# breakout.net
KiCad netlist of a schematic drawn in EAGLE
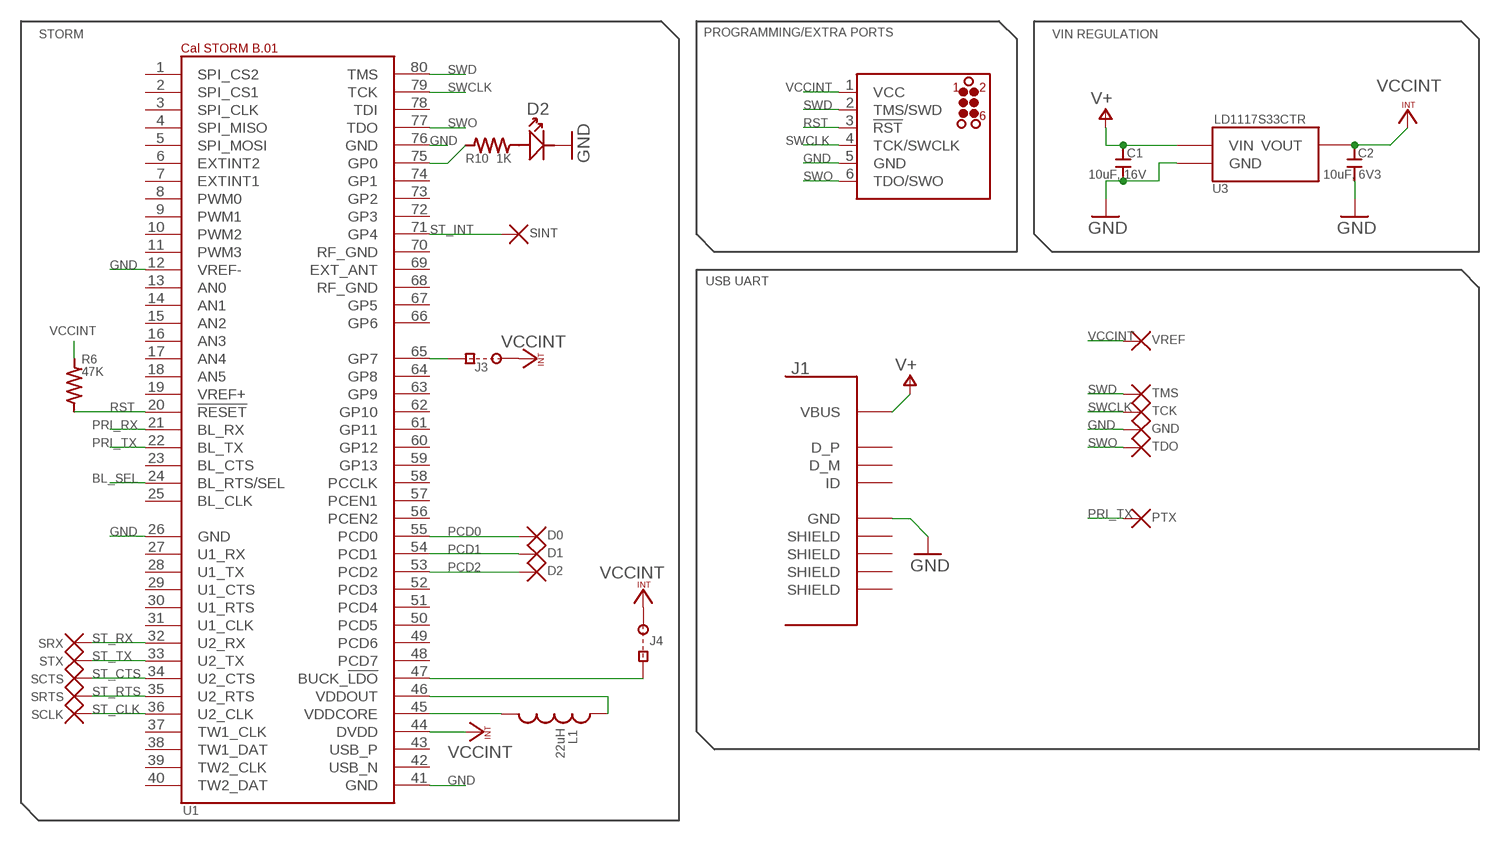
[diagram p0: schematic, sheet 1]

(export (version "E")
  (design (tool "Eeschema 10.0.6"))
  (components
    (comp (ref "C1")
      (value "10uF, 16V")
      (footprint "eagle-import:0805")
      (libsource (lib "eagle-import") (part "0805_CAPACITOR"))
    )
    (comp (ref "C2")
      (value "10uF, 6V3")
      (footprint "eagle-import:C0603")
      (libsource (lib "eagle-import") (part "0603_CAPACITOR"))
    )
    (comp (ref "D2")
      (value "STATLED")
      (footprint "eagle-import:LINE_0805")
      (libsource (lib "eagle-import") (part "STATLED"))
    )
    (comp (ref "J1")
      (value "USBSMT")
      (footprint "eagle-import:USB_SMT")
      (libsource (lib "eagle-import") (part "USBSMT"))
    )
    (comp (ref "J3")
      (value "CUTJ")
      (footprint "eagle-import:CUT")
      (libsource (lib "eagle-import") (part "CUTJ"))
    )
    (comp (ref "J4")
      (value "CUTJ")
      (footprint "eagle-import:CUT")
      (libsource (lib "eagle-import") (part "CUTJ"))
    )
    (comp (ref "J8")
      (value "JLINK_CONNECT")
      (footprint "eagle-import:TC2030-MCP-NL")
      (libsource (lib "eagle-import") (part "JLINK_CONNECT"))
    )
    (comp (ref "L1")
      (value "22uH")
      (footprint "eagle-import:SRN4018")
      (libsource (lib "eagle-import") (part "SRN4018"))
    )
    (comp (ref "R6")
      (value "47K")
      (footprint "eagle-import:C0402")
      (libsource (lib "eagle-import") (part "0603_RESISTOR0402"))
    )
    (comp (ref "R10")
      (value "1K")
      (footprint "eagle-import:C0402")
      (libsource (lib "eagle-import") (part "0603_RESISTOR0402"))
    )
    (comp (ref "TP1")
      (value "VREF")
      (footprint "eagle-import:TPP")
      (libsource (lib "eagle-import") (part "TP"))
    )
    (comp (ref "TP4")
      (value "TMS")
      (footprint "eagle-import:TPP")
      (libsource (lib "eagle-import") (part "TP"))
    )
    (comp (ref "TP5")
      (value "TCK")
      (footprint "eagle-import:TPP")
      (libsource (lib "eagle-import") (part "TP"))
    )
    (comp (ref "TP6")
      (value "GND")
      (footprint "eagle-import:TPP")
      (libsource (lib "eagle-import") (part "TP"))
    )
    (comp (ref "TP7")
      (value "TDO")
      (footprint "eagle-import:TPP")
      (libsource (lib "eagle-import") (part "TP"))
    )
    (comp (ref "TP10")
      (value "D2")
      (footprint "eagle-import:TPP")
      (libsource (lib "eagle-import") (part "TP"))
    )
    (comp (ref "TP11")
      (value "D1")
      (footprint "eagle-import:TPP")
      (libsource (lib "eagle-import") (part "TP"))
    )
    (comp (ref "TP12")
      (value "D0")
      (footprint "eagle-import:TPP")
      (libsource (lib "eagle-import") (part "TP"))
    )
    (comp (ref "TP13")
      (value "SRX")
      (footprint "eagle-import:TPP")
      (libsource (lib "eagle-import") (part "TP"))
    )
    (comp (ref "TP14")
      (value "STX")
      (footprint "eagle-import:TPP")
      (libsource (lib "eagle-import") (part "TP"))
    )
    (comp (ref "TP15")
      (value "SCTS")
      (footprint "eagle-import:TPP")
      (libsource (lib "eagle-import") (part "TP"))
    )
    (comp (ref "TP16")
      (value "SRTS")
      (footprint "eagle-import:TPP")
      (libsource (lib "eagle-import") (part "TP"))
    )
    (comp (ref "TP17")
      (value "SCLK")
      (footprint "eagle-import:TPP")
      (libsource (lib "eagle-import") (part "TP"))
    )
    (comp (ref "TP18")
      (value "SINT")
      (footprint "eagle-import:TPP")
      (libsource (lib "eagle-import") (part "TP"))
    )
    (comp (ref "TX")
      (value "PTX")
      (footprint "eagle-import:TPP")
      (libsource (lib "eagle-import") (part "TP"))
    )
    (comp (ref "U1")
      (value "STORM_B.01")
      (footprint "eagle-import:STORM_LANDING")
      (libsource (lib "eagle-import") (part "STORM_B.01"))
    )
    (comp (ref "U3")
      (value "LD1117S33CTR_3V3_REG")
      (footprint "eagle-import:SOT223")
      (libsource (lib "eagle-import") (part "LD1117S33CTR_3V3_REG"))
    )
  )
  (nets
    (net (code "1") (name "/BL_SEL") (class "Default")
      (node (ref "U1") (pin "24") (pinfunction "BL_RTS/SEL_24") (pintype "bidirectional"))
    )
    (net (code "2") (name "/PCD0") (class "Default")
      (node (ref "TP12") (pin "P$1") (pinfunction "P$1_P$1") (pintype "bidirectional"))
      (node (ref "U1") (pin "55") (pinfunction "PCD0_55") (pintype "bidirectional"))
    )
    (net (code "3") (name "/PCD1") (class "Default")
      (node (ref "TP11") (pin "P$1") (pinfunction "P$1_P$1") (pintype "bidirectional"))
      (node (ref "U1") (pin "54") (pinfunction "PCD1_54") (pintype "bidirectional"))
    )
    (net (code "4") (name "/PCD2") (class "Default")
      (node (ref "TP10") (pin "P$1") (pinfunction "P$1_P$1") (pintype "bidirectional"))
      (node (ref "U1") (pin "53") (pinfunction "PCD2_53") (pintype "bidirectional"))
    )
    (net (code "5") (name "/PRI_RX") (class "Default")
      (node (ref "U1") (pin "21") (pinfunction "BL_RX_21") (pintype "bidirectional"))
    )
    (net (code "6") (name "/PRI_TX") (class "Default")
      (node (ref "TX") (pin "P$1") (pinfunction "P$1_P$1") (pintype "bidirectional"))
      (node (ref "U1") (pin "22") (pinfunction "BL_TX_22") (pintype "bidirectional"))
    )
    (net (code "7") (name "/RST") (class "Default")
      (node (ref "J8") (pin "3") (pinfunction "~{RST}_3") (pintype "bidirectional"))
      (node (ref "R6") (pin "2") (pinfunction "P$2_2") (pintype "passive"))
      (node (ref "U1") (pin "20") (pinfunction "~{RESET}_20") (pintype "bidirectional"))
    )
    (net (code "8") (name "/ST_CLK") (class "Default")
      (node (ref "TP17") (pin "P$1") (pinfunction "P$1_P$1") (pintype "bidirectional"))
      (node (ref "U1") (pin "36") (pinfunction "U2_CLK_36") (pintype "bidirectional"))
    )
    (net (code "9") (name "/ST_CTS") (class "Default")
      (node (ref "TP15") (pin "P$1") (pinfunction "P$1_P$1") (pintype "bidirectional"))
      (node (ref "U1") (pin "34") (pinfunction "U2_CTS_34") (pintype "bidirectional"))
    )
    (net (code "10") (name "/ST_INT") (class "Default")
      (node (ref "TP18") (pin "P$1") (pinfunction "P$1_P$1") (pintype "bidirectional"))
      (node (ref "U1") (pin "71") (pinfunction "GP4_71") (pintype "bidirectional"))
    )
    (net (code "11") (name "/ST_RTS") (class "Default")
      (node (ref "TP16") (pin "P$1") (pinfunction "P$1_P$1") (pintype "bidirectional"))
      (node (ref "U1") (pin "35") (pinfunction "U2_RTS_35") (pintype "bidirectional"))
    )
    (net (code "12") (name "/ST_RX") (class "Default")
      (node (ref "TP13") (pin "P$1") (pinfunction "P$1_P$1") (pintype "bidirectional"))
      (node (ref "U1") (pin "32") (pinfunction "U2_RX_32") (pintype "bidirectional"))
    )
    (net (code "13") (name "/ST_TX") (class "Default")
      (node (ref "TP14") (pin "P$1") (pinfunction "P$1_P$1") (pintype "bidirectional"))
      (node (ref "U1") (pin "33") (pinfunction "U2_TX_33") (pintype "bidirectional"))
    )
    (net (code "14") (name "/SWCLK") (class "Default")
      (node (ref "J8") (pin "4") (pinfunction "TCK/SWCLK_4") (pintype "bidirectional"))
      (node (ref "TP5") (pin "P$1") (pinfunction "P$1_P$1") (pintype "bidirectional"))
      (node (ref "U1") (pin "79") (pinfunction "TCK_79") (pintype "bidirectional"))
    )
    (net (code "15") (name "/SWD") (class "Default")
      (node (ref "J8") (pin "2") (pinfunction "TMS/SWD_2") (pintype "bidirectional"))
      (node (ref "TP4") (pin "P$1") (pinfunction "P$1_P$1") (pintype "bidirectional"))
      (node (ref "U1") (pin "80") (pinfunction "TMS_80") (pintype "bidirectional"))
    )
    (net (code "16") (name "/SWO") (class "Default")
      (node (ref "J8") (pin "6") (pinfunction "TDO/SWO_6") (pintype "bidirectional"))
      (node (ref "TP7") (pin "P$1") (pinfunction "P$1_P$1") (pintype "bidirectional"))
      (node (ref "U1") (pin "77") (pinfunction "TDO_77") (pintype "bidirectional"))
    )
    (net (code "17") (name "GND") (class "Default")
      (node (ref "C1") (pin "1") (pinfunction "P$1_1") (pintype "passive"))
      (node (ref "C2") (pin "1") (pinfunction "P$1_1") (pintype "passive"))
      (node (ref "D2") (pin "LINE") (pinfunction "-_LINE") (pintype "passive"))
      (node (ref "J1") (pin "5GND") (pinfunction "GND_5GND") (pintype "bidirectional"))
      (node (ref "J8") (pin "5") (pinfunction "GND_5") (pintype "power_in"))
      (node (ref "TP6") (pin "P$1") (pinfunction "P$1_P$1") (pintype "bidirectional"))
      (node (ref "U1") (pin "12") (pinfunction "VREF-_12") (pintype "bidirectional"))
      (node (ref "U1") (pin "26") (pinfunction "GND_26") (pintype "bidirectional"))
      (node (ref "U1") (pin "41") (pinfunction "GND_41") (pintype "bidirectional"))
      (node (ref "U1") (pin "76") (pinfunction "GND_76") (pintype "bidirectional"))
      (node (ref "U3") (pin "1") (pinfunction "GND_1") (pintype "bidirectional"))
    )
    (net (code "18") (name "Net-(D2-+)") (class "Default")
      (node (ref "D2") (pin "NOLINE") (pinfunction "+_NOLINE") (pintype "passive"))
      (node (ref "R10") (pin "2") (pinfunction "P$2_2") (pintype "passive"))
    )
    (net (code "19") (name "Net-(R10-P$1)") (class "Default")
      (node (ref "R10") (pin "1") (pinfunction "P$1_1") (pintype "passive"))
      (node (ref "U1") (pin "75") (pinfunction "GP0_75") (pintype "bidirectional"))
    )
    (net (code "20") (name "Net-(U1-BUCK_~{LDO})") (class "Default")
      (node (ref "J4") (pin "SQ") (pinfunction "SQ_SQ") (pintype "bidirectional"))
      (node (ref "U1") (pin "47") (pinfunction "BUCK_~{LDO}_47") (pintype "bidirectional"))
    )
    (net (code "21") (name "Net-(U1-GP7)") (class "Default")
      (node (ref "J3") (pin "SQ") (pinfunction "SQ_SQ") (pintype "bidirectional"))
      (node (ref "U1") (pin "65") (pinfunction "GP7_65") (pintype "bidirectional"))
    )
    (net (code "22") (name "Net-(U1-VDDCORE)") (class "Default")
      (node (ref "L1") (pin "P$2") (pinfunction "P$2_P$2") (pintype "passive"))
      (node (ref "U1") (pin "45") (pinfunction "VDDCORE_45") (pintype "bidirectional"))
    )
    (net (code "23") (name "Net-(U1-VDDOUT)") (class "Default")
      (node (ref "L1") (pin "P$1") (pinfunction "P$1_P$1") (pintype "passive"))
      (node (ref "U1") (pin "46") (pinfunction "VDDOUT_46") (pintype "bidirectional"))
    )
    (net (code "24") (name "V+") (class "Default")
      (node (ref "C1") (pin "2") (pinfunction "P$2_2") (pintype "passive"))
      (node (ref "J1") (pin "1VBUS") (pinfunction "VBUS_1VBUS") (pintype "bidirectional"))
      (node (ref "U3") (pin "3") (pinfunction "VIN_3") (pintype "bidirectional"))
    )
    (net (code "25") (name "VCCINT") (class "Default")
      (node (ref "C2") (pin "2") (pinfunction "P$2_2") (pintype "passive"))
      (node (ref "J3") (pin "R") (pinfunction "R_R") (pintype "bidirectional"))
      (node (ref "J4") (pin "R") (pinfunction "R_R") (pintype "bidirectional"))
      (node (ref "J8") (pin "1") (pinfunction "VCC_1") (pintype "passive"))
      (node (ref "R6") (pin "1") (pinfunction "P$1_1") (pintype "passive"))
      (node (ref "TP1") (pin "P$1") (pinfunction "P$1_P$1") (pintype "bidirectional"))
      (node (ref "U1") (pin "44") (pinfunction "DVDD_44") (pintype "bidirectional"))
      (node (ref "U3") (pin "2") (pinfunction "VOUT_2") (pintype "bidirectional"))
    )
    (net (code "26") (name "unconnected-(J1-D_M-Pad2D-)") (class "Default")
      (node (ref "J1") (pin "2D-") (pinfunction "D_M_2D-") (pintype "bidirectional"))
    )
    (net (code "27") (name "unconnected-(J1-D_P-Pad3D+)") (class "Default")
      (node (ref "J1") (pin "3D+") (pinfunction "D_P_3D+") (pintype "bidirectional"))
    )
    (net (code "28") (name "unconnected-(J1-ID-Pad4ID)") (class "Default")
      (node (ref "J1") (pin "4ID") (pinfunction "ID_4ID") (pintype "bidirectional"))
    )
    (net (code "29") (name "unconnected-(J1-SHIELD-PadSHIELD@1)") (class "Default")
      (node (ref "J1") (pin "SHIELD@1") (pinfunction "SHIELD_SHIELD@1") (pintype "no_connect"))
    )
    (net (code "30") (name "unconnected-(J1-SHIELD-PadSHIELD@2)") (class "Default")
      (node (ref "J1") (pin "SHIELD@2") (pinfunction "SHIELD_SHIELD@2") (pintype "no_connect"))
    )
    (net (code "31") (name "unconnected-(J1-SHIELD-PadSHIELD@3)") (class "Default")
      (node (ref "J1") (pin "SHIELD@3") (pinfunction "SHIELD_SHIELD@3") (pintype "no_connect"))
    )
    (net (code "32") (name "unconnected-(J1-SHIELD-PadSHIELD@4)") (class "Default")
      (node (ref "J1") (pin "SHIELD@4") (pinfunction "SHIELD_SHIELD@4") (pintype "no_connect"))
    )
    (net (code "33") (name "unconnected-(U1-AN0-Pad13)") (class "Default")
      (node (ref "U1") (pin "13") (pinfunction "AN0_13") (pintype "bidirectional"))
    )
    (net (code "34") (name "unconnected-(U1-AN1-Pad14)") (class "Default")
      (node (ref "U1") (pin "14") (pinfunction "AN1_14") (pintype "bidirectional"))
    )
    (net (code "35") (name "unconnected-(U1-AN2-Pad15)") (class "Default")
      (node (ref "U1") (pin "15") (pinfunction "AN2_15") (pintype "bidirectional"))
    )
    (net (code "36") (name "unconnected-(U1-AN3-Pad16)") (class "Default")
      (node (ref "U1") (pin "16") (pinfunction "AN3_16") (pintype "bidirectional"))
    )
    (net (code "37") (name "unconnected-(U1-AN4-Pad17)") (class "Default")
      (node (ref "U1") (pin "17") (pinfunction "AN4_17") (pintype "bidirectional"))
    )
    (net (code "38") (name "unconnected-(U1-AN5-Pad18)") (class "Default")
      (node (ref "U1") (pin "18") (pinfunction "AN5_18") (pintype "bidirectional"))
    )
    (net (code "39") (name "unconnected-(U1-BL_CLK-Pad25)") (class "Default")
      (node (ref "U1") (pin "25") (pinfunction "BL_CLK_25") (pintype "bidirectional"))
    )
    (net (code "40") (name "unconnected-(U1-BL_CTS-Pad23)") (class "Default")
      (node (ref "U1") (pin "23") (pinfunction "BL_CTS_23") (pintype "bidirectional"))
    )
    (net (code "41") (name "unconnected-(U1-EXTINT1-Pad7)") (class "Default")
      (node (ref "U1") (pin "7") (pinfunction "EXTINT1_7") (pintype "bidirectional"))
    )
    (net (code "42") (name "unconnected-(U1-EXTINT2-Pad6)") (class "Default")
      (node (ref "U1") (pin "6") (pinfunction "EXTINT2_6") (pintype "bidirectional"))
    )
    (net (code "43") (name "unconnected-(U1-EXT_ANT-Pad69)") (class "Default")
      (node (ref "U1") (pin "69") (pinfunction "EXT_ANT_69") (pintype "bidirectional"))
    )
    (net (code "44") (name "unconnected-(U1-GP1-Pad74)") (class "Default")
      (node (ref "U1") (pin "74") (pinfunction "GP1_74") (pintype "bidirectional"))
    )
    (net (code "45") (name "unconnected-(U1-GP2-Pad73)") (class "Default")
      (node (ref "U1") (pin "73") (pinfunction "GP2_73") (pintype "bidirectional"))
    )
    (net (code "46") (name "unconnected-(U1-GP3-Pad72)") (class "Default")
      (node (ref "U1") (pin "72") (pinfunction "GP3_72") (pintype "bidirectional"))
    )
    (net (code "47") (name "unconnected-(U1-GP5-Pad67)") (class "Default")
      (node (ref "U1") (pin "67") (pinfunction "GP5_67") (pintype "bidirectional"))
    )
    (net (code "48") (name "unconnected-(U1-GP6-Pad66)") (class "Default")
      (node (ref "U1") (pin "66") (pinfunction "GP6_66") (pintype "bidirectional"))
    )
    (net (code "49") (name "unconnected-(U1-GP8-Pad64)") (class "Default")
      (node (ref "U1") (pin "64") (pinfunction "GP8_64") (pintype "bidirectional"))
    )
    (net (code "50") (name "unconnected-(U1-GP9-Pad63)") (class "Default")
      (node (ref "U1") (pin "63") (pinfunction "GP9_63") (pintype "bidirectional"))
    )
    (net (code "51") (name "unconnected-(U1-GP10-Pad62)") (class "Default")
      (node (ref "U1") (pin "62") (pinfunction "GP10_62") (pintype "bidirectional"))
    )
    (net (code "52") (name "unconnected-(U1-GP11-Pad61)") (class "Default")
      (node (ref "U1") (pin "61") (pinfunction "GP11_61") (pintype "bidirectional"))
    )
    (net (code "53") (name "unconnected-(U1-GP12-Pad60)") (class "Default")
      (node (ref "U1") (pin "60") (pinfunction "GP12_60") (pintype "bidirectional"))
    )
    (net (code "54") (name "unconnected-(U1-GP13-Pad59)") (class "Default")
      (node (ref "U1") (pin "59") (pinfunction "GP13_59") (pintype "bidirectional"))
    )
    (net (code "55") (name "unconnected-(U1-PCCLK-Pad58)") (class "Default")
      (node (ref "U1") (pin "58") (pinfunction "PCCLK_58") (pintype "bidirectional"))
    )
    (net (code "56") (name "unconnected-(U1-PCD3-Pad52)") (class "Default")
      (node (ref "U1") (pin "52") (pinfunction "PCD3_52") (pintype "bidirectional"))
    )
    (net (code "57") (name "unconnected-(U1-PCD4-Pad51)") (class "Default")
      (node (ref "U1") (pin "51") (pinfunction "PCD4_51") (pintype "bidirectional"))
    )
    (net (code "58") (name "unconnected-(U1-PCD5-Pad50)") (class "Default")
      (node (ref "U1") (pin "50") (pinfunction "PCD5_50") (pintype "bidirectional"))
    )
    (net (code "59") (name "unconnected-(U1-PCD6-Pad49)") (class "Default")
      (node (ref "U1") (pin "49") (pinfunction "PCD6_49") (pintype "bidirectional"))
    )
    (net (code "60") (name "unconnected-(U1-PCD7-Pad48)") (class "Default")
      (node (ref "U1") (pin "48") (pinfunction "PCD7_48") (pintype "bidirectional"))
    )
    (net (code "61") (name "unconnected-(U1-PCEN1-Pad57)") (class "Default")
      (node (ref "U1") (pin "57") (pinfunction "PCEN1_57") (pintype "bidirectional"))
    )
    (net (code "62") (name "unconnected-(U1-PCEN2-Pad56)") (class "Default")
      (node (ref "U1") (pin "56") (pinfunction "PCEN2_56") (pintype "bidirectional"))
    )
    (net (code "63") (name "unconnected-(U1-PWM0-Pad8)") (class "Default")
      (node (ref "U1") (pin "8") (pinfunction "PWM0_8") (pintype "bidirectional"))
    )
    (net (code "64") (name "unconnected-(U1-PWM1-Pad9)") (class "Default")
      (node (ref "U1") (pin "9") (pinfunction "PWM1_9") (pintype "bidirectional"))
    )
    (net (code "65") (name "unconnected-(U1-PWM2-Pad10)") (class "Default")
      (node (ref "U1") (pin "10") (pinfunction "PWM2_10") (pintype "bidirectional"))
    )
    (net (code "66") (name "unconnected-(U1-PWM3-Pad11)") (class "Default")
      (node (ref "U1") (pin "11") (pinfunction "PWM3_11") (pintype "bidirectional"))
    )
    (net (code "67") (name "unconnected-(U1-RF_GND-Pad68)") (class "Default")
      (node (ref "U1") (pin "68") (pinfunction "RF_GND_68") (pintype "bidirectional"))
    )
    (net (code "68") (name "unconnected-(U1-RF_GND-Pad70)") (class "Default")
      (node (ref "U1") (pin "70") (pinfunction "RF_GND_70") (pintype "bidirectional"))
    )
    (net (code "69") (name "unconnected-(U1-SPI_CLK-Pad3)") (class "Default")
      (node (ref "U1") (pin "3") (pinfunction "SPI_CLK_3") (pintype "bidirectional"))
    )
    (net (code "70") (name "unconnected-(U1-SPI_CS1-Pad2)") (class "Default")
      (node (ref "U1") (pin "2") (pinfunction "SPI_CS1_2") (pintype "bidirectional"))
    )
    (net (code "71") (name "unconnected-(U1-SPI_CS2-Pad1)") (class "Default")
      (node (ref "U1") (pin "1") (pinfunction "SPI_CS2_1") (pintype "bidirectional"))
    )
    (net (code "72") (name "unconnected-(U1-SPI_MISO-Pad4)") (class "Default")
      (node (ref "U1") (pin "4") (pinfunction "SPI_MISO_4") (pintype "bidirectional"))
    )
    (net (code "73") (name "unconnected-(U1-SPI_MOSI-Pad5)") (class "Default")
      (node (ref "U1") (pin "5") (pinfunction "SPI_MOSI_5") (pintype "bidirectional"))
    )
    (net (code "74") (name "unconnected-(U1-TDI-Pad78)") (class "Default")
      (node (ref "U1") (pin "78") (pinfunction "TDI_78") (pintype "bidirectional"))
    )
    (net (code "75") (name "unconnected-(U1-TW1_CLK-Pad37)") (class "Default")
      (node (ref "U1") (pin "37") (pinfunction "TW1_CLK_37") (pintype "bidirectional"))
    )
    (net (code "76") (name "unconnected-(U1-TW1_DAT-Pad38)") (class "Default")
      (node (ref "U1") (pin "38") (pinfunction "TW1_DAT_38") (pintype "bidirectional"))
    )
    (net (code "77") (name "unconnected-(U1-TW2_CLK-Pad39)") (class "Default")
      (node (ref "U1") (pin "39") (pinfunction "TW2_CLK_39") (pintype "bidirectional"))
    )
    (net (code "78") (name "unconnected-(U1-TW2_DAT-Pad40)") (class "Default")
      (node (ref "U1") (pin "40") (pinfunction "TW2_DAT_40") (pintype "bidirectional"))
    )
    (net (code "79") (name "unconnected-(U1-U1_CLK-Pad31)") (class "Default")
      (node (ref "U1") (pin "31") (pinfunction "U1_CLK_31") (pintype "bidirectional"))
    )
    (net (code "80") (name "unconnected-(U1-U1_CTS-Pad29)") (class "Default")
      (node (ref "U1") (pin "29") (pinfunction "U1_CTS_29") (pintype "bidirectional"))
    )
    (net (code "81") (name "unconnected-(U1-U1_RTS-Pad30)") (class "Default")
      (node (ref "U1") (pin "30") (pinfunction "U1_RTS_30") (pintype "bidirectional"))
    )
    (net (code "82") (name "unconnected-(U1-U1_RX-Pad27)") (class "Default")
      (node (ref "U1") (pin "27") (pinfunction "U1_RX_27") (pintype "bidirectional"))
    )
    (net (code "83") (name "unconnected-(U1-U1_TX-Pad28)") (class "Default")
      (node (ref "U1") (pin "28") (pinfunction "U1_TX_28") (pintype "bidirectional"))
    )
    (net (code "84") (name "unconnected-(U1-USB_N-Pad42)") (class "Default")
      (node (ref "U1") (pin "42") (pinfunction "USB_N_42") (pintype "bidirectional"))
    )
    (net (code "85") (name "unconnected-(U1-USB_P-Pad43)") (class "Default")
      (node (ref "U1") (pin "43") (pinfunction "USB_P_43") (pintype "bidirectional"))
    )
    (net (code "86") (name "unconnected-(U1-VREF+-Pad19)") (class "Default")
      (node (ref "U1") (pin "19") (pinfunction "VREF+_19") (pintype "bidirectional"))
    )
  )
)
